# audio.net
KiCad netlist of a schematic drawn in Altium Designer
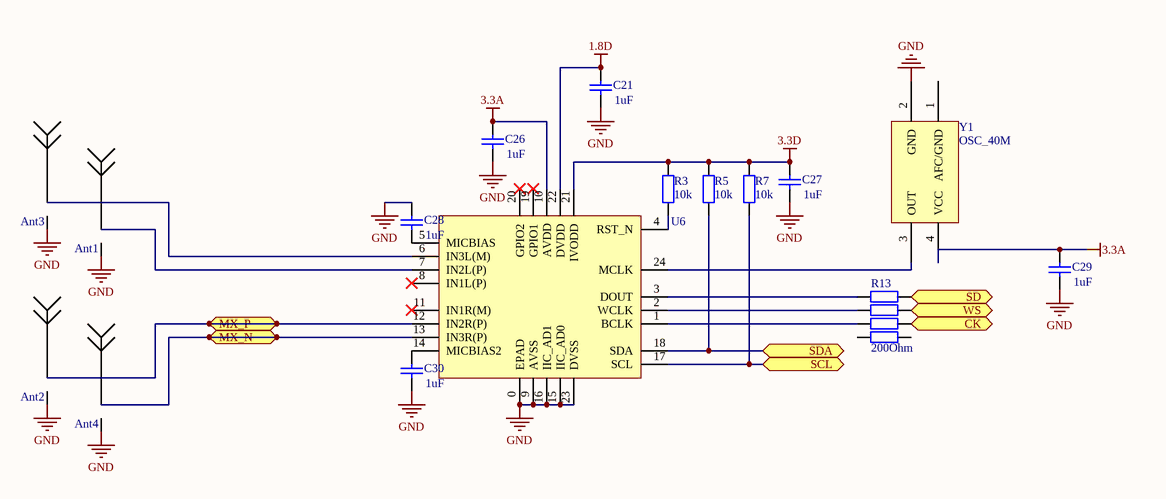
[diagram p0: audio.SchDoc]

(export (version "E")
  (design (tool "Eeschema 10.0.6"))
  (components
    (comp (ref "Ant1") (value "Antenna") (footprint "BK5811:SMA") (libsource (lib "F4SDR") (part "Antenna")))
    (comp (ref "Ant2") (value "Antenna") (footprint "BK5811:SMA") (libsource (lib "F4SDR") (part "Antenna")))
    (comp (ref "Ant3") (value "Antenna") (footprint "BK5811:SMA") (libsource (lib "F4SDR") (part "Antenna")))
    (comp (ref "Ant4") (value "Antenna") (footprint "BK5811:SMA") (libsource (lib "F4SDR") (part "Antenna")))
    (comp (ref "C21")
      (value "1uF")
      (footprint "0402")
      (description "Capacitor")
      (libsource (lib "RTC6705") (part "Cap"))
    )
    (comp (ref "C26")
      (value "1uF")
      (footprint "0402")
      (description "Capacitor")
      (libsource (lib "RTC6705") (part "Cap"))
    )
    (comp (ref "C27")
      (value "1uF")
      (footprint "0402")
      (description "Capacitor")
      (libsource (lib "RTC6705") (part "Cap"))
    )
    (comp (ref "C28")
      (value "1uF")
      (footprint "0402")
      (description "Capacitor")
      (libsource (lib "RTC6705") (part "Cap"))
    )
    (comp (ref "C29")
      (value "1uF")
      (footprint "0402")
      (description "Capacitor")
      (libsource (lib "RTC6705") (part "Cap"))
    )
    (comp (ref "C30")
      (value "1uF")
      (footprint "0402")
      (description "Capacitor")
      (libsource (lib "RTC6705") (part "Cap"))
    )
    (comp (ref "R3")
      (value "10k")
      (footprint "0402")
      (description "Resistor")
      (fields (field (name "Comment") "Res2") (field (name "PUBLISHER") "Altium Limited"))
      (libsource (lib "RTC6705") (part "Res2"))
    )
    (comp (ref "R5")
      (value "10k")
      (footprint "0402")
      (description "Resistor")
      (fields (field (name "Comment") "Res2") (field (name "PUBLISHER") "Altium Limited"))
      (libsource (lib "RTC6705") (part "Res2"))
    )
    (comp (ref "R7")
      (value "10k")
      (footprint "0402")
      (description "Resistor")
      (fields (field (name "Comment") "Res2") (field (name "PUBLISHER") "Altium Limited"))
      (libsource (lib "RTC6705") (part "Res2"))
    )
    (comp (ref "R13")
      (value "200Ohm")
      (footprint "0402X4")
      (description "Resistor")
      (fields (field (name "Comment") "Res*4") (field (name "PUBLISHER") "Altium Limited"))
      (libsource (lib "sch") (part "Res*4"))
    )
    (comp (ref "U6")
      (value "TLV320ADC3101")
      (footprint "TLV320ADC3101")
      (libsource (lib "ADAU1761") (part "TLV320ADC3101"))
    )
    (comp (ref "Y1") (value "OSC_40M") (footprint "TXC_7Q") (libsource (lib "F4SDR") (part "OSC_40M")))
  )
  (nets
    (net (code "1") (name "/CK") (class "Default")
      (node (ref "R13") (pin "2") (pinfunction "2_2") (pintype "passive"))
    )
    (net (code "2") (name "/MX_N") (class "Default")
      (node (ref "Ant4") (pin "1") (pinfunction "1_1") (pintype "passive"))
      (node (ref "U6") (pin "13") (pinfunction "IN3R(P)_13") (pintype "passive"))
    )
    (net (code "3") (name "/MX_P") (class "Default")
      (node (ref "Ant2") (pin "1") (pinfunction "1_1") (pintype "passive"))
      (node (ref "U6") (pin "12") (pinfunction "IN2R(P)_12") (pintype "passive"))
    )
    (net (code "4") (name "/SCL") (class "Default")
      (node (ref "R7") (pin "1") (pinfunction "1_1") (pintype "passive"))
      (node (ref "U6") (pin "17") (pinfunction "SCL_17") (pintype "passive"))
    )
    (net (code "5") (name "/SD") (class "Default")
      (node (ref "R13") (pin "4") (pinfunction "4_4") (pintype "passive"))
    )
    (net (code "6") (name "/SDA") (class "Default")
      (node (ref "R5") (pin "1") (pinfunction "1_1") (pintype "passive"))
      (node (ref "U6") (pin "18") (pinfunction "SDA_18") (pintype "passive"))
    )
    (net (code "7") (name "/WS") (class "Default")
      (node (ref "R13") (pin "3") (pinfunction "3_3") (pintype "passive"))
    )
    (net (code "8") (name "1.8D") (class "Default")
      (node (ref "C21") (pin "2") (pinfunction "2_2") (pintype "passive"))
      (node (ref "U6") (pin "22") (pinfunction "DVDD_22") (pintype "passive"))
    )
    (net (code "9") (name "3.3A") (class "Default")
      (node (ref "C26") (pin "2") (pinfunction "2_2") (pintype "passive"))
      (node (ref "C29") (pin "2") (pinfunction "2_2") (pintype "passive"))
      (node (ref "U6") (pin "10") (pinfunction "AVDD_10") (pintype "passive"))
      (node (ref "Y1") (pin "4") (pinfunction "VCC_4") (pintype "passive"))
    )
    (net (code "10") (name "3.3D") (class "Default")
      (node (ref "C27") (pin "2") (pinfunction "2_2") (pintype "passive"))
      (node (ref "R3") (pin "2") (pinfunction "2_2") (pintype "passive"))
      (node (ref "R5") (pin "2") (pinfunction "2_2") (pintype "passive"))
      (node (ref "R7") (pin "2") (pinfunction "2_2") (pintype "passive"))
      (node (ref "U6") (pin "21") (pinfunction "IVODD_21") (pintype "passive"))
    )
    (net (code "11") (name "GND") (class "Default")
      (node (ref "Ant1") (pin "GND") (pinfunction "G_GND") (pintype "passive"))
      (node (ref "Ant2") (pin "GND") (pinfunction "G_GND") (pintype "passive"))
      (node (ref "Ant3") (pin "GND") (pinfunction "G_GND") (pintype "passive"))
      (node (ref "Ant4") (pin "GND") (pinfunction "G_GND") (pintype "passive"))
      (node (ref "C21") (pin "1") (pinfunction "1_1") (pintype "passive"))
      (node (ref "C26") (pin "1") (pinfunction "1_1") (pintype "passive"))
      (node (ref "C27") (pin "1") (pinfunction "1_1") (pintype "passive"))
      (node (ref "C28") (pin "2") (pinfunction "2_2") (pintype "passive"))
      (node (ref "C29") (pin "1") (pinfunction "1_1") (pintype "passive"))
      (node (ref "C30") (pin "1") (pinfunction "1_1") (pintype "passive"))
      (node (ref "U6") (pin "0") (pinfunction "EPAD_0") (pintype "passive"))
      (node (ref "U6") (pin "15") (pinfunction "IIC_AD0_15") (pintype "passive"))
      (node (ref "U6") (pin "16") (pinfunction "IIC_AD1_16") (pintype "passive"))
      (node (ref "U6") (pin "23") (pinfunction "DVSS_23") (pintype "passive"))
      (node (ref "U6") (pin "9") (pinfunction "AVSS_9") (pintype "passive"))
      (node (ref "Y1") (pin "2") (pinfunction "GND_2") (pintype "passive"))
    )
    (net (code "12") (name "Net-(U6-BCLK)") (class "Default")
      (node (ref "R13") (pin "7") (pinfunction "7_7") (pintype "passive"))
      (node (ref "U6") (pin "1") (pinfunction "BCLK_1") (pintype "passive"))
    )
    (net (code "13") (name "Net-(U6-DOUT)") (class "Default")
      (node (ref "R13") (pin "5") (pinfunction "5_5") (pintype "passive"))
      (node (ref "U6") (pin "3") (pinfunction "DOUT_3") (pintype "passive"))
    )
    (net (code "14") (name "Net-(U6-IN2L(P))") (class "Default")
      (node (ref "Ant1") (pin "1") (pinfunction "1_1") (pintype "passive"))
      (node (ref "U6") (pin "7") (pinfunction "IN2L(P)_7") (pintype "passive"))
    )
    (net (code "15") (name "Net-(U6-IN3L(M))") (class "Default")
      (node (ref "Ant3") (pin "1") (pinfunction "1_1") (pintype "passive"))
      (node (ref "U6") (pin "6") (pinfunction "IN3L(M)_6") (pintype "passive"))
    )
    (net (code "16") (name "Net-(U6-MCLK)") (class "Default")
      (node (ref "U6") (pin "24") (pinfunction "MCLK_24") (pintype "passive"))
      (node (ref "Y1") (pin "3") (pinfunction "OUT_3") (pintype "passive"))
    )
    (net (code "17") (name "Net-(U6-MICBIAS)") (class "Default")
      (node (ref "C28") (pin "1") (pinfunction "1_1") (pintype "passive"))
      (node (ref "U6") (pin "5") (pinfunction "MICBIAS_5") (pintype "passive"))
    )
    (net (code "18") (name "Net-(U6-MICBIAS2)") (class "Default")
      (node (ref "C30") (pin "2") (pinfunction "2_2") (pintype "passive"))
      (node (ref "U6") (pin "14") (pinfunction "MICBIAS2_14") (pintype "passive"))
    )
    (net (code "19") (name "Net-(U6-RST_N)") (class "Default")
      (node (ref "R3") (pin "1") (pinfunction "1_1") (pintype "passive"))
      (node (ref "U6") (pin "4") (pinfunction "RST_N_4") (pintype "passive"))
    )
    (net (code "20") (name "Net-(U6-WCLK)") (class "Default")
      (node (ref "R13") (pin "6") (pinfunction "6_6") (pintype "passive"))
      (node (ref "U6") (pin "2") (pinfunction "WCLK_2") (pintype "passive"))
    )
    (net (code "21") (name "unconnected-(R13-Pad1)") (class "Default")
      (node (ref "R13") (pin "1") (pinfunction "1_1") (pintype "passive"))
    )
    (net (code "22") (name "unconnected-(R13-Pad8)") (class "Default")
      (node (ref "R13") (pin "8") (pinfunction "8_8") (pintype "passive"))
    )
    (net (code "23") (name "unconnected-(U6-GPIO1-Pad19)") (class "Default")
      (node (ref "U6") (pin "19") (pinfunction "GPIO1_19") (pintype "passive+no_connect"))
    )
    (net (code "24") (name "unconnected-(U6-GPIO2-Pad20)") (class "Default")
      (node (ref "U6") (pin "20") (pinfunction "GPIO2_20") (pintype "passive+no_connect"))
    )
    (net (code "25") (name "unconnected-(U6-IN1L(P)-Pad8)") (class "Default")
      (node (ref "U6") (pin "8") (pinfunction "IN1L(P)_8") (pintype "passive+no_connect"))
    )
    (net (code "26") (name "unconnected-(U6-IN1R(M)-Pad11)") (class "Default")
      (node (ref "U6") (pin "11") (pinfunction "IN1R(M)_11") (pintype "passive+no_connect"))
    )
    (net (code "27") (name "unconnected-(Y1-AFC{slash}GND-Pad1)") (class "Default")
      (node (ref "Y1") (pin "1") (pinfunction "AFC/GND_1") (pintype "passive"))
    )
  )
)
